# Mic_preamp_schematic.net
KiCad netlist of a schematic drawn in Altium Designer
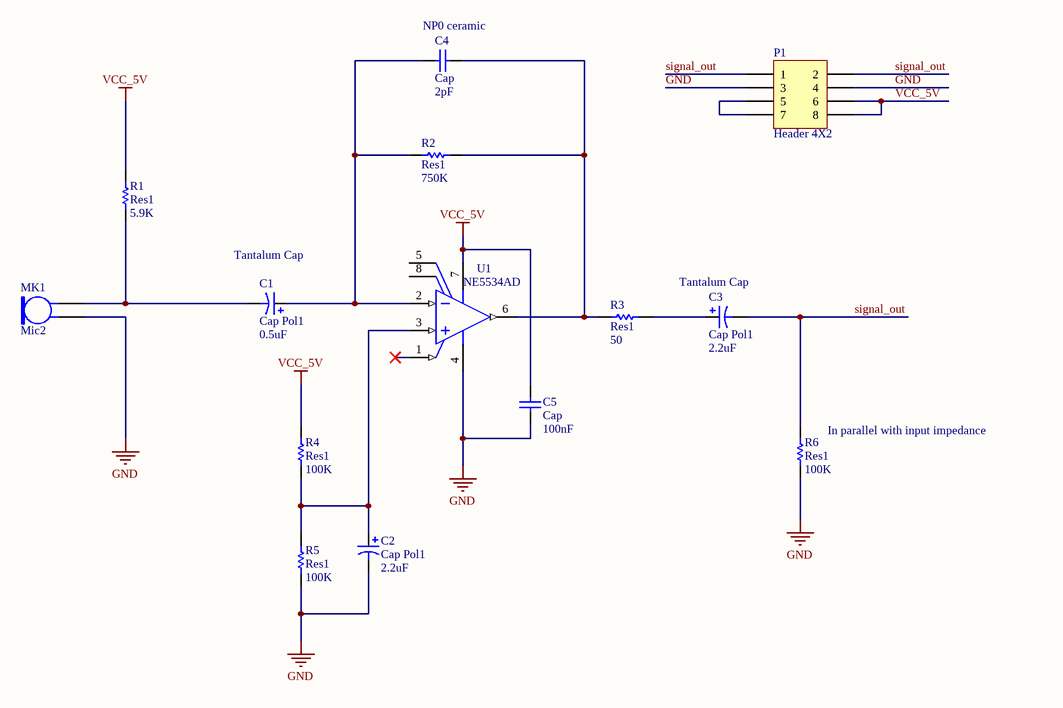
[diagram p0: Mic_preamp_schematic.SchDoc]

(export (version "E")
  (design (tool "Eeschema 10.0.6"))
  (components
    (comp (ref "C1")
      (value "Cap Pol1")
      (footprint "CAPC3216X175N")
      (description "Polarized Capacitor (Radial)")
      (fields (field (name "ALTIUM_VALUE") "0.5uF") (field (name "PUBLISHER") "Altium Limited"))
      (libsource (lib "Miscellaneous Devices") (part "Cap Pol1"))
    )
    (comp (ref "C2")
      (value "Cap Pol1")
      (footprint "CAPC3216X175N")
      (description "Polarized Capacitor (Radial)")
      (fields (field (name "ALTIUM_VALUE") "2.2uF") (field (name "PUBLISHER") "Altium Limited"))
      (libsource (lib "Miscellaneous Devices") (part "Cap Pol1"))
    )
    (comp (ref "C3")
      (value "Cap Pol1")
      (footprint "CAPC3216X175N")
      (description "Polarized Capacitor (Radial)")
      (fields (field (name "ALTIUM_VALUE") "2.2uF") (field (name "PUBLISHER") "Altium Limited"))
      (libsource (lib "Miscellaneous Devices") (part "Cap Pol1"))
    )
    (comp (ref "C4")
      (value "Cap")
      (footprint "CAPC2012X135N")
      (description "Capacitor")
      (fields (field (name "ALTIUM_VALUE") "2pF") (field (name "PUBLISHER") "Altium Limited"))
      (libsource (lib "Miscellaneous Devices") (part "Cap"))
    )
    (comp (ref "C5")
      (value "Cap")
      (footprint "CAPC2012X135N")
      (description "Capacitor")
      (fields (field (name "ALTIUM_VALUE") "100nF") (field (name "PUBLISHER") "Altium Limited"))
      (libsource (lib "Miscellaneous Devices") (part "Cap"))
    )
    (comp (ref "MK1")
      (value "Mic2")
      (footprint "LD-MC-6035P")
      (description "Microphone")
      (fields (field (name "PUBLISHER") "Altium Limited"))
      (libsource (lib "Miscellaneous Devices") (part "Mic2"))
    )
    (comp (ref "P1")
      (value "Header 4X2")
      (footprint "HDR2X4")
      (description "Header, 4-Pin, Dual row")
      (fields (field (name "PUBLISHER") "Altium Limited"))
      (libsource (lib "Miscellaneous Connectors") (part "Header 4X2"))
    )
    (comp (ref "R1")
      (value "Res1")
      (footprint "RESC2012X70N")
      (description "Resistor")
      (fields (field (name "ALTIUM_VALUE") "5.9K") (field (name "PUBLISHER") "Altium Limited"))
      (libsource (lib "Miscellaneous Devices") (part "Res1"))
    )
    (comp (ref "R2")
      (value "Res1")
      (footprint "RESC2012X70N")
      (description "Resistor")
      (fields (field (name "ALTIUM_VALUE") "750K") (field (name "PUBLISHER") "Altium Limited"))
      (libsource (lib "Miscellaneous Devices") (part "Res1"))
    )
    (comp (ref "R3")
      (value "Res1")
      (footprint "RESC2012X70N")
      (description "Resistor")
      (fields (field (name "ALTIUM_VALUE") "50") (field (name "PUBLISHER") "Altium Limited"))
      (libsource (lib "Miscellaneous Devices") (part "Res1"))
    )
    (comp (ref "R4")
      (value "Res1")
      (footprint "RESC2012X70N")
      (description "Resistor")
      (fields (field (name "ALTIUM_VALUE") "100K") (field (name "PUBLISHER") "Altium Limited"))
      (libsource (lib "Miscellaneous Devices") (part "Res1"))
    )
    (comp (ref "R5")
      (value "Res1")
      (footprint "RESC2012X70N")
      (description "Resistor")
      (fields (field (name "ALTIUM_VALUE") "100K") (field (name "PUBLISHER") "Altium Limited"))
      (libsource (lib "Miscellaneous Devices") (part "Res1"))
    )
    (comp (ref "R6")
      (value "Res1")
      (footprint "RESC2012X70N")
      (description "Resistor")
      (fields (field (name "ALTIUM_VALUE") "100K") (field (name "PUBLISHER") "Altium Limited"))
      (libsource (lib "Miscellaneous Devices") (part "Res1"))
    )
    (comp (ref "U1")
      (value "NE5534AD")
      (footprint "TI-D8_N")
      (fields (field (name "MANUFACTURER") "Texas Instruments"))
      (libsource (lib "TI Amplifiers and Linear Operational Amplifier General Purpose") (part "NE5534AD"))
    )
  )
  (nets
    (net (code "1") (name "/signal_out") (class "Default")
      (node (ref "C3") (pin "2") (pinfunction "2_2") (pintype "passive"))
      (node (ref "P1") (pin "1") (pinfunction "1_1") (pintype "passive"))
      (node (ref "P1") (pin "2") (pinfunction "2_2") (pintype "passive"))
      (node (ref "R6") (pin "2") (pinfunction "2_2") (pintype "passive"))
    )
    (net (code "2") (name "GND") (class "Default")
      (node (ref "C2") (pin "2") (pinfunction "2_2") (pintype "passive"))
      (node (ref "C5") (pin "1") (pinfunction "1_1") (pintype "passive"))
      (node (ref "MK1") (pin "1") (pinfunction "1_1") (pintype "passive"))
      (node (ref "P1") (pin "3") (pinfunction "3_3") (pintype "passive"))
      (node (ref "P1") (pin "4") (pinfunction "4_4") (pintype "passive"))
      (node (ref "R5") (pin "2") (pinfunction "2_2") (pintype "passive"))
      (node (ref "R6") (pin "1") (pinfunction "1_1") (pintype "passive"))
      (node (ref "U1") (pin "4") (pinfunction "VCC-_4") (pintype "power_in"))
    )
    (net (code "3") (name "Net-(C1-Pad2)") (class "Default")
      (node (ref "C1") (pin "2") (pinfunction "2_2") (pintype "passive"))
      (node (ref "MK1") (pin "2") (pinfunction "2_2") (pintype "passive"))
      (node (ref "R1") (pin "1") (pinfunction "1_1") (pintype "passive"))
    )
    (net (code "4") (name "Net-(C3-Pad1)") (class "Default")
      (node (ref "C3") (pin "1") (pinfunction "1_1") (pintype "passive"))
      (node (ref "R3") (pin "1") (pinfunction "1_1") (pintype "passive"))
    )
    (net (code "5") (name "Net-(P1-Pad5)") (class "Default")
      (node (ref "P1") (pin "5") (pinfunction "5_5") (pintype "passive"))
      (node (ref "P1") (pin "7") (pinfunction "7_7") (pintype "passive"))
    )
    (net (code "6") (name "Net-(U1-IN+)") (class "Default")
      (node (ref "C2") (pin "1") (pinfunction "1_1") (pintype "passive"))
      (node (ref "R4") (pin "2") (pinfunction "2_2") (pintype "passive"))
      (node (ref "R5") (pin "1") (pinfunction "1_1") (pintype "passive"))
      (node (ref "U1") (pin "3") (pinfunction "IN+_3") (pintype "input"))
    )
    (net (code "7") (name "Net-(U1-IN-)") (class "Default")
      (node (ref "C1") (pin "1") (pinfunction "1_1") (pintype "passive"))
      (node (ref "C4") (pin "1") (pinfunction "1_1") (pintype "passive"))
      (node (ref "R2") (pin "2") (pinfunction "2_2") (pintype "passive"))
      (node (ref "U1") (pin "2") (pinfunction "IN-_2") (pintype "input"))
    )
    (net (code "8") (name "Net-(U1-OUT)") (class "Default")
      (node (ref "C4") (pin "2") (pinfunction "2_2") (pintype "passive"))
      (node (ref "R2") (pin "1") (pinfunction "1_1") (pintype "passive"))
      (node (ref "R3") (pin "2") (pinfunction "2_2") (pintype "passive"))
      (node (ref "U1") (pin "6") (pinfunction "OUT_6") (pintype "output"))
    )
    (net (code "9") (name "VCC_5V") (class "Default")
      (node (ref "C5") (pin "2") (pinfunction "2_2") (pintype "passive"))
      (node (ref "P1") (pin "6") (pinfunction "6_6") (pintype "passive"))
      (node (ref "P1") (pin "8") (pinfunction "8_8") (pintype "passive"))
      (node (ref "R1") (pin "2") (pinfunction "2_2") (pintype "passive"))
      (node (ref "R4") (pin "1") (pinfunction "1_1") (pintype "passive"))
      (node (ref "U1") (pin "7") (pinfunction "VCC+_7") (pintype "power_in"))
    )
    (net (code "10") (name "unconnected-(U1-BALANCE-Pad1)") (class "Default")
      (node (ref "U1") (pin "1") (pinfunction "BALANCE_1") (pintype "input+no_connect"))
    )
    (net (code "11") (name "unconnected-(U1-COMP-Pad5)") (class "Default")
      (node (ref "U1") (pin "5") (pinfunction "COMP_5") (pintype "passive"))
    )
    (net (code "12") (name "unconnected-(U1-COMP{slash}BAL-Pad8)") (class "Default")
      (node (ref "U1") (pin "8") (pinfunction "COMP/BAL_8") (pintype "passive"))
    )
  )
)
